# Low_Pass_Filter.net
KiCad netlist of a schematic drawn in Altium Designer
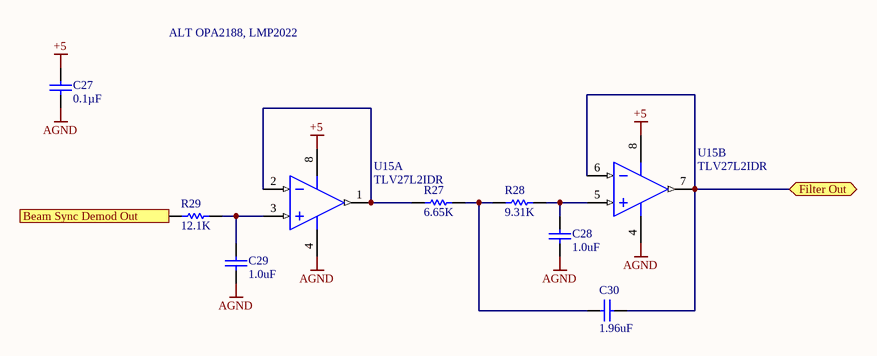
[diagram p0: Low Pass Filter.SchDoc]

(export (version "E")
  (design (tool "Eeschema 10.0.6"))
  (components
    (comp (ref "C27")
      (value "CAP CER 0.1UF 25V X7R 0805")
      (footprint "CAPC0805(2012)145_N")
      (fields
        (field (name "MANUFACTURER") "Murata Electronics North America")
        (field (name "MANUFACTURER PART NUMBER") "GRM21BR71E104KA01L")
        (field (name "CAPACITANCE") "0.1µF")
        (field (name "TOLERANCE") "±10%")
      )
      (libsource (lib "Altium Content Vault") (part "CMP-1036-04795-1"))
    )
    (comp (ref "C28")
      (value "1.0uF")
      (footprint "CAPC0805(2012)75_L")
      (description "CAP CER 1.0UF 25V X5R 0805")
      (libsource (lib "Altium Content Vault") (part "CMP-1036-02117-1"))
    )
    (comp (ref "C29")
      (value "1.0uF")
      (footprint "CAPC0805(2012)75_L")
      (description "CAP CER 1.0UF 25V X5R 0805")
      (fields (field (name "TOLERANCE") "±20%"))
      (libsource (lib "Altium Content Vault") (part "CMP-1036-02117-1"))
    )
    (comp (ref "C30")
      (value "1.96uF")
      (footprint "CAPC0805(2012)75_L")
      (description "CAP CER 1.96UF 25V X5R 0805")
      (libsource (lib "Altium Content Vault") (part "CMP-1036-02117-1"))
    )
    (comp (ref "R27")
      (value "6.65K")
      (footprint "RESC0805(2012)_L")
      (description "RES SMD 6.65K OHM 1% 1/8W 0805")
      (libsource (lib "Altium Content Vault") (part "CMP-1013-00215-1"))
    )
    (comp (ref "R28")
      (value "9.31K")
      (footprint "RESC0805(2012)_L")
      (description "RES SMD 9.31K OHM 1% 1/8W 0805")
      (libsource (lib "Altium Content Vault") (part "CMP-1013-00215-1"))
    )
    (comp (ref "R29")
      (value "12.1K")
      (footprint "RESC0805(2012)_L")
      (description "RES SMD 12.1K OHM 1% 1/8W 0805")
      (libsource (lib "Altium Content Vault") (part "CMP-1013-00215-1"))
    )
    (comp (ref "U15")
      (value "TLV27L2IDR")
      (footprint "D0008A_L")
      (fields (field (name "MANUFACTURER") "Texas Instruments"))
      (libsource (lib "Altium Content Vault") (part "TI-TLV_TLC-8"))
    )
  )
  (nets
    (net (code "1") (name "+5") (class "Default")
      (node (ref "C27") (pin "2") (pinfunction "2_2") (pintype "passive"))
      (node (ref "U15") (pin "8") (pinfunction "VDD_8") (pintype "power_in"))
    )
    (net (code "2") (name "/Beam Sync Demod Out") (class "Default")
      (node (ref "R29") (pin "2") (pinfunction "2_2") (pintype "passive"))
    )
    (net (code "3") (name "/Filter Out") (class "Default")
      (node (ref "C30") (pin "1") (pinfunction "1_1") (pintype "passive"))
      (node (ref "U15") (pin "6") (pinfunction "IN2-_6") (pintype "input"))
      (node (ref "U15") (pin "7") (pinfunction "OUT2_7") (pintype "output"))
    )
    (net (code "4") (name "AGND") (class "Default")
      (node (ref "C27") (pin "1") (pinfunction "1_1") (pintype "passive"))
      (node (ref "C28") (pin "1") (pinfunction "1_1") (pintype "passive"))
      (node (ref "C29") (pin "1") (pinfunction "1_1") (pintype "passive"))
      (node (ref "U15") (pin "4") (pinfunction "GND_4") (pintype "power_in"))
    )
    (net (code "5") (name "Net-(C30-Pad2)") (class "Default")
      (node (ref "C30") (pin "2") (pinfunction "2_2") (pintype "passive"))
      (node (ref "R27") (pin "1") (pinfunction "1_1") (pintype "passive"))
      (node (ref "R28") (pin "2") (pinfunction "2_2") (pintype "passive"))
    )
    (net (code "6") (name "Net-(U15A-IN1+)") (class "Default")
      (node (ref "C29") (pin "2") (pinfunction "2_2") (pintype "passive"))
      (node (ref "R29") (pin "1") (pinfunction "1_1") (pintype "passive"))
      (node (ref "U15") (pin "3") (pinfunction "IN1+_3") (pintype "input"))
    )
    (net (code "7") (name "Net-(U15A-IN1-)") (class "Default")
      (node (ref "R27") (pin "2") (pinfunction "2_2") (pintype "passive"))
      (node (ref "U15") (pin "1") (pinfunction "OUT1_1") (pintype "output"))
      (node (ref "U15") (pin "2") (pinfunction "IN1-_2") (pintype "input"))
    )
    (net (code "8") (name "Net-(U15B-IN2+)") (class "Default")
      (node (ref "C28") (pin "2") (pinfunction "2_2") (pintype "passive"))
      (node (ref "R28") (pin "1") (pinfunction "1_1") (pintype "passive"))
      (node (ref "U15") (pin "5") (pinfunction "IN2+_5") (pintype "input"))
    )
  )
)
